# ospi_v142.net
KiCad netlist of a schematic drawn in EAGLE
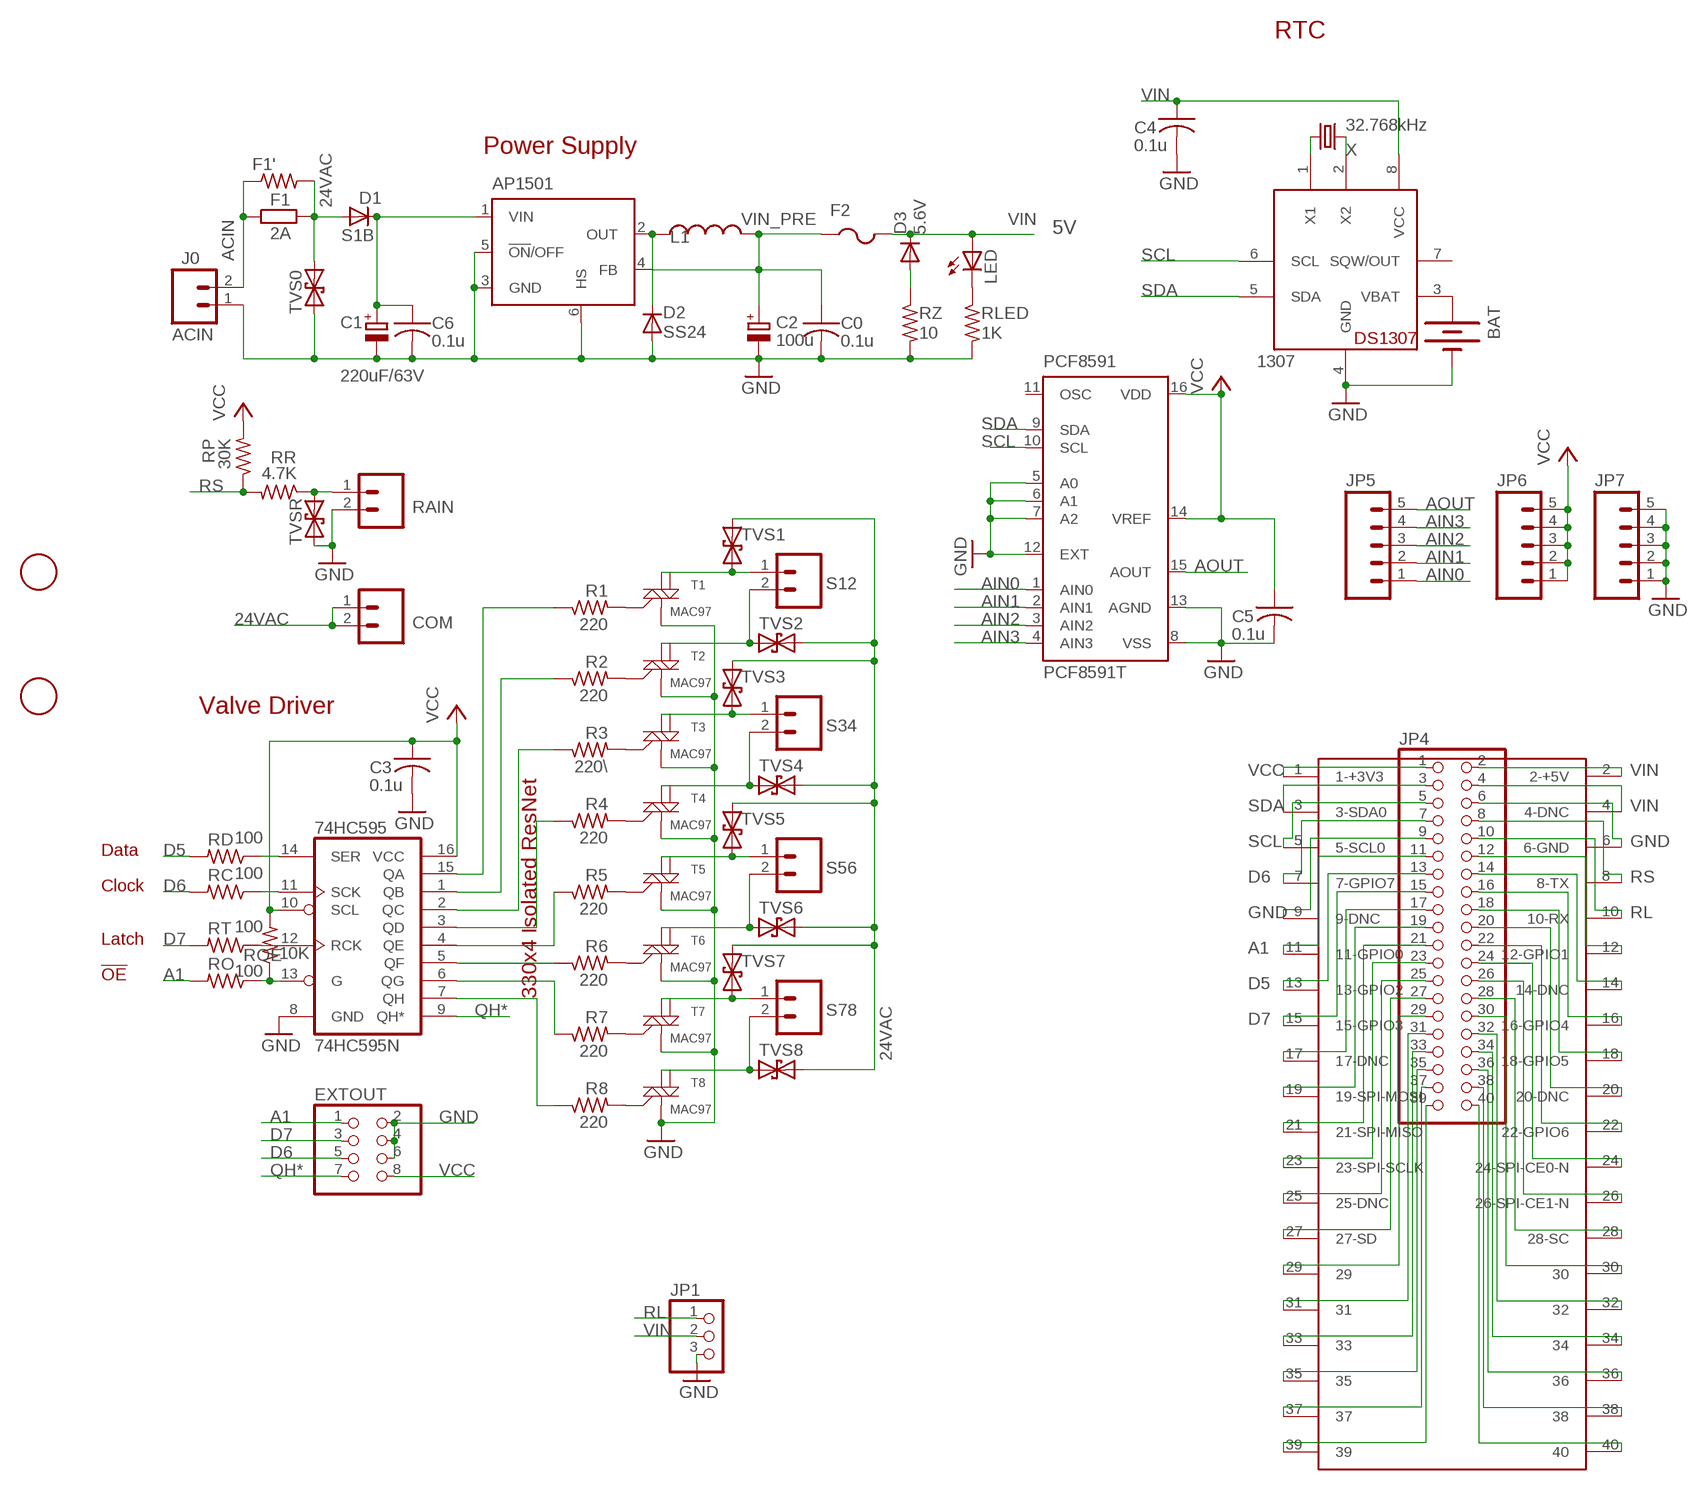
[diagram p0: schematic, sheet 1]

(export (version "E")
  (design (tool "Eeschema 10.0.6"))
  (components
    (comp (ref "74HC595")
      (value "74HC595N")
      (footprint "eagle-import:SO16")
      (libsource (lib "eagle-import") (part "74595DLS"))
    )
    (comp (ref "1307")
      (value "DS1307")
      (footprint "eagle-import:SO08")
      (libsource (lib "eagle-import") (part "DS1307SOIC"))
    )
    (comp (ref "AP1501")
      (value "LM2596S")
      (footprint "eagle-import:TO263-5")
      (fields (field (name "MF") "NATIONAL SEMICONDUCTOR") (field (name "MPN") "LM2596S-ADJ/NOPB"))
      (libsource (lib "eagle-import") (part "LM2596S"))
    )
    (comp (ref "BAT")
      (value "BATTERYBATTERY_12MM_SMT")
      (footprint "eagle-import:BATTCON_12MM_SMT")
      (libsource (lib "eagle-import") (part "BATTERYBATTERY_12MM_SMT"))
    )
    (comp (ref "C0")
      (value "0.1u")
      (footprint "eagle-import:C0603K")
      (libsource (lib "eagle-import") (part "C-USC0603K"))
    )
    (comp (ref "C1")
      (value "220uF/63V")
      (footprint "eagle-import:PANASONIC_E")
      (libsource (lib "eagle-import") (part "CPOL-EUE"))
    )
    (comp (ref "C2")
      (value "100u")
      (footprint "eagle-import:PANASONIC_E")
      (libsource (lib "eagle-import") (part "CPOL-EUE"))
    )
    (comp (ref "C3")
      (value "0.1u")
      (footprint "eagle-import:C0603K")
      (libsource (lib "eagle-import") (part "C-USC0603K"))
    )
    (comp (ref "C4")
      (value "0.1u")
      (footprint "eagle-import:C0603K")
      (libsource (lib "eagle-import") (part "C-USC0603K"))
    )
    (comp (ref "C5")
      (value "0.1u")
      (footprint "eagle-import:C0603K")
      (libsource (lib "eagle-import") (part "C-USC0603K"))
    )
    (comp (ref "C6")
      (value "0.1u")
      (footprint "eagle-import:C0603K")
      (libsource (lib "eagle-import") (part "C-USC0603K"))
    )
    (comp (ref "COM")
      (value "M025MM-X")
      (footprint "eagle-import:SCREWTERMINAL-5MM-2-X")
      (libsource (lib "eagle-import") (part "M025MM-X"))
    )
    (comp (ref "D1")
      (value "S1B")
      (footprint "eagle-import:DO-214AC")
      (libsource (lib "eagle-import") (part "DIODE-DO-214AC"))
    )
    (comp (ref "D2")
      (value "SS24")
      (footprint "eagle-import:SMB")
      (libsource (lib "eagle-import") (part "DIODE-SMB"))
    )
    (comp (ref "D3")
      (value "5.6V")
      (footprint "eagle-import:MINIMELF")
      (libsource (lib "eagle-import") (part "DIODE-MINIMELF"))
    )
    (comp (ref "EXTOUT")
      (value "PINHD-2X4/90")
      (footprint "eagle-import:2X04_90")
      (libsource (lib "eagle-import") (part "PINHD-2X4/90"))
    )
    (comp (ref "F1")
      (value "2A")
      (footprint "eagle-import:0414V")
      (libsource (lib "eagle-import") (part "R-EU_0414/5V"))
    )
    (comp (ref "F1'")
      (value "R-US_R1206")
      (footprint "eagle-import:R1206")
      (libsource (lib "eagle-import") (part "adafruitGood_R-US_R1206"))
    )
    (comp (ref "F2")
      (value "PTCFUSE-1812")
      (footprint "eagle-import:1812")
      (libsource (lib "eagle-import") (part "PTCFUSE-1812"))
    )
    (comp (ref "J0")
      (value "ACIN")
      (footprint "eagle-import:SCREWTERMINAL-4MM-2-X")
      (libsource (lib "eagle-import") (part "M024MM-X"))
    )
    (comp (ref "JP1")
      (value "PINHD-1X3")
      (footprint "eagle-import:1X03")
      (libsource (lib "eagle-import") (part "PINHD-1X3"))
    )
    (comp (ref "JP4")
      (value "PINHD-2X20")
      (footprint "eagle-import:2X20")
      (libsource (lib "eagle-import") (part "PINHD-2X20"))
    )
    (comp (ref "JP5")
      (value "M05PTH")
      (footprint "eagle-import:1X05")
      (libsource (lib "eagle-import") (part "M05PTH"))
    )
    (comp (ref "JP6")
      (value "M05PTH")
      (footprint "eagle-import:1X05")
      (libsource (lib "eagle-import") (part "M05PTH"))
    )
    (comp (ref "JP7")
      (value "M05PTH")
      (footprint "eagle-import:1X05")
      (libsource (lib "eagle-import") (part "M05PTH"))
    )
    (comp (ref "L1")
      (value "150uH")
      (footprint "eagle-import:CDRH125")
      (libsource (lib "eagle-import") (part "INDUCTORPWR"))
    )
    (comp (ref "LED")
      (value "LEDCHIPLED_0805")
      (footprint "eagle-import:CHIPLED_0805")
      (libsource (lib "eagle-import") (part "LEDCHIPLED_0805"))
    )
    (comp (ref "PCF8591")
      (value "PCF8591T")
      (footprint "eagle-import:SO16W")
      (fields (field (name "MPN") "PCF8591T/2,512"))
      (libsource (lib "eagle-import") (part "PCF8591T"))
    )
    (comp (ref "R1")
      (value "220")
      (footprint "eagle-import:R0603")
      (libsource (lib "eagle-import") (part "R-US_R0603"))
    )
    (comp (ref "R2")
      (value "220")
      (footprint "eagle-import:R0603")
      (libsource (lib "eagle-import") (part "R-US_R0603"))
    )
    (comp (ref "R3")
      (value "220\\")
      (footprint "eagle-import:R0603")
      (libsource (lib "eagle-import") (part "R-US_R0603"))
    )
    (comp (ref "R4")
      (value "220")
      (footprint "eagle-import:R0603")
      (libsource (lib "eagle-import") (part "R-US_R0603"))
    )
    (comp (ref "R5")
      (value "220")
      (footprint "eagle-import:R0603")
      (libsource (lib "eagle-import") (part "R-US_R0603"))
    )
    (comp (ref "R6")
      (value "220")
      (footprint "eagle-import:R0603")
      (libsource (lib "eagle-import") (part "R-US_R0603"))
    )
    (comp (ref "R7")
      (value "220")
      (footprint "eagle-import:R0603")
      (libsource (lib "eagle-import") (part "R-US_R0603"))
    )
    (comp (ref "R8")
      (value "220")
      (footprint "eagle-import:R0603")
      (libsource (lib "eagle-import") (part "R-US_R0603"))
    )
    (comp (ref "RAIN")
      (value "M025MM-X")
      (footprint "eagle-import:SCREWTERMINAL-5MM-2-X")
      (libsource (lib "eagle-import") (part "M025MM-X"))
    )
    (comp (ref "RC")
      (value "100")
      (footprint "eagle-import:R0603")
      (libsource (lib "eagle-import") (part "R-US_R0603"))
    )
    (comp (ref "RD")
      (value "100")
      (footprint "eagle-import:R0603")
      (libsource (lib "eagle-import") (part "R-US_R0603"))
    )
    (comp (ref "RLED")
      (value "1K")
      (footprint "eagle-import:R0805")
      (libsource (lib "eagle-import") (part "R-US_R0805"))
    )
    (comp (ref "RO")
      (value "100")
      (footprint "eagle-import:R0603")
      (libsource (lib "eagle-import") (part "R-US_R0603"))
    )
    (comp (ref "ROE")
      (value "10K")
      (footprint "eagle-import:R0603")
      (libsource (lib "eagle-import") (part "R-US_R0603"))
    )
    (comp (ref "RP")
      (value "30K")
      (footprint "eagle-import:R0805")
      (libsource (lib "eagle-import") (part "R-US_R0805"))
    )
    (comp (ref "RR")
      (value "4.7K")
      (footprint "eagle-import:R0805")
      (libsource (lib "eagle-import") (part "R-US_R0805"))
    )
    (comp (ref "RT")
      (value "100")
      (footprint "eagle-import:R0603")
      (libsource (lib "eagle-import") (part "R-US_R0603"))
    )
    (comp (ref "RZ")
      (value "10")
      (footprint "eagle-import:R0805")
      (libsource (lib "eagle-import") (part "R-US_R0805"))
    )
    (comp (ref "S12")
      (value "M025MM-X")
      (footprint "eagle-import:SCREWTERMINAL-5MM-2-X")
      (libsource (lib "eagle-import") (part "M025MM-X"))
    )
    (comp (ref "S34")
      (value "M025MM-X")
      (footprint "eagle-import:SCREWTERMINAL-5MM-2-X")
      (libsource (lib "eagle-import") (part "M025MM-X"))
    )
    (comp (ref "S56")
      (value "M025MM-X")
      (footprint "eagle-import:SCREWTERMINAL-5MM-2-X")
      (libsource (lib "eagle-import") (part "M025MM-X"))
    )
    (comp (ref "S78")
      (value "M025MM-X")
      (footprint "eagle-import:SCREWTERMINAL-5MM-2-X")
      (libsource (lib "eagle-import") (part "M025MM-X"))
    )
    (comp (ref "T1")
      (value "MAC97")
      (footprint "eagle-import:SOT223")
      (libsource (lib "eagle-import") (part "MAC97SOT223"))
    )
    (comp (ref "T2")
      (value "MAC97")
      (footprint "eagle-import:SOT223")
      (libsource (lib "eagle-import") (part "MAC97SOT223"))
    )
    (comp (ref "T3")
      (value "MAC97")
      (footprint "eagle-import:SOT223")
      (libsource (lib "eagle-import") (part "MAC97SOT223"))
    )
    (comp (ref "T4")
      (value "MAC97")
      (footprint "eagle-import:SOT223")
      (libsource (lib "eagle-import") (part "MAC97SOT223"))
    )
    (comp (ref "T5")
      (value "MAC97")
      (footprint "eagle-import:SOT223")
      (libsource (lib "eagle-import") (part "MAC97SOT223"))
    )
    (comp (ref "T6")
      (value "MAC97")
      (footprint "eagle-import:SOT223")
      (libsource (lib "eagle-import") (part "MAC97SOT223"))
    )
    (comp (ref "T7")
      (value "MAC97")
      (footprint "eagle-import:SOT223")
      (libsource (lib "eagle-import") (part "MAC97SOT223"))
    )
    (comp (ref "T8")
      (value "MAC97")
      (footprint "eagle-import:SOT223")
      (libsource (lib "eagle-import") (part "MAC97SOT223"))
    )
    (comp (ref "TVS0")
      (value "TVSSMB")
      (footprint "eagle-import:SMB")
      (libsource (lib "eagle-import") (part "TVSSMB"))
    )
    (comp (ref "TVS1")
      (value "TVSSMB")
      (footprint "eagle-import:SMB")
      (libsource (lib "eagle-import") (part "TVSSMB"))
    )
    (comp (ref "TVS2")
      (value "TVSSMB")
      (footprint "eagle-import:SMB")
      (libsource (lib "eagle-import") (part "TVSSMB"))
    )
    (comp (ref "TVS3")
      (value "TVSSMB")
      (footprint "eagle-import:SMB")
      (libsource (lib "eagle-import") (part "TVSSMB"))
    )
    (comp (ref "TVS4")
      (value "TVSSMB")
      (footprint "eagle-import:SMB")
      (libsource (lib "eagle-import") (part "TVSSMB"))
    )
    (comp (ref "TVS5")
      (value "TVSSMB")
      (footprint "eagle-import:SMB")
      (libsource (lib "eagle-import") (part "TVSSMB"))
    )
    (comp (ref "TVS6")
      (value "TVSSMB")
      (footprint "eagle-import:SMB")
      (libsource (lib "eagle-import") (part "TVSSMB"))
    )
    (comp (ref "TVS7")
      (value "TVSSMB")
      (footprint "eagle-import:SMB")
      (libsource (lib "eagle-import") (part "TVSSMB"))
    )
    (comp (ref "TVS8")
      (value "TVSSMB")
      (footprint "eagle-import:SMB")
      (libsource (lib "eagle-import") (part "TVSSMB"))
    )
    (comp (ref "TVSR")
      (value "TVSSMB")
      (footprint "eagle-import:SMB")
      (libsource (lib "eagle-import") (part "TVSSMB"))
    )
    (comp (ref "U$1")
      (value "FIDUCIAL")
      (footprint "eagle-import:FIDUCIAL_1MM")
      (libsource (lib "eagle-import") (part "FIDUCIAL"))
    )
    (comp (ref "U$2")
      (value "RPIB+")
      (footprint "eagle-import:RPIB+")
      (libsource (lib "eagle-import") (part "RPIB+"))
    )
    (comp (ref "U$3")
      (value "FIDUCIAL")
      (footprint "eagle-import:FIDUCIAL_1MM")
      (libsource (lib "eagle-import") (part "FIDUCIAL"))
    )
    (comp (ref "X")
      (value "32.768kHz")
      (footprint "eagle-import:MM20SS")
      (libsource (lib "eagle-import") (part "CRYSTALMM20SS"))
    )
  )
  (nets
    (net (code "1") (name "/24VAC") (class "Default")
      (node (ref "COM") (pin "1") (pinfunction "1_1") (pintype "passive"))
      (node (ref "COM") (pin "2") (pinfunction "2_2") (pintype "passive"))
      (node (ref "D1") (pin "A") (pinfunction "A_A") (pintype "passive"))
      (node (ref "F1") (pin "2") (pinfunction "2_2") (pintype "passive"))
      (node (ref "F1'") (pin "2") (pinfunction "2_2") (pintype "passive"))
      (node (ref "TVS0") (pin "C") (pinfunction "C_C") (pintype "passive"))
      (node (ref "TVS1") (pin "C") (pinfunction "C_C") (pintype "passive"))
      (node (ref "TVS2") (pin "C") (pinfunction "C_C") (pintype "passive"))
      (node (ref "TVS3") (pin "C") (pinfunction "C_C") (pintype "passive"))
      (node (ref "TVS4") (pin "C") (pinfunction "C_C") (pintype "passive"))
      (node (ref "TVS5") (pin "C") (pinfunction "C_C") (pintype "passive"))
      (node (ref "TVS6") (pin "C") (pinfunction "C_C") (pintype "passive"))
      (node (ref "TVS7") (pin "C") (pinfunction "C_C") (pintype "passive"))
      (node (ref "TVS8") (pin "C") (pinfunction "C_C") (pintype "passive"))
    )
    (net (code "2") (name "/A1") (class "Default")
      (node (ref "EXTOUT") (pin "1") (pinfunction "1_1") (pintype "passive"))
      (node (ref "JP4") (pin "11") (pinfunction "11_11") (pintype "passive"))
      (node (ref "RO") (pin "2") (pinfunction "2_2") (pintype "passive"))
      (node (ref "U$2") (pin "11") (pinfunction "11-GPIO0_11") (pintype "bidirectional"))
    )
    (net (code "3") (name "/ACIN") (class "Default")
      (node (ref "F1") (pin "1") (pinfunction "1_1") (pintype "passive"))
      (node (ref "F1'") (pin "1") (pinfunction "1_1") (pintype "passive"))
      (node (ref "J0") (pin "2") (pinfunction "2_2") (pintype "passive"))
    )
    (net (code "4") (name "/AIN0") (class "Default")
      (node (ref "JP5") (pin "1") (pinfunction "1_1") (pintype "passive"))
      (node (ref "PCF8591") (pin "1") (pinfunction "AIN0_1") (pintype "input"))
    )
    (net (code "5") (name "/AIN1") (class "Default")
      (node (ref "JP5") (pin "2") (pinfunction "2_2") (pintype "passive"))
      (node (ref "PCF8591") (pin "2") (pinfunction "AIN1_2") (pintype "input"))
    )
    (net (code "6") (name "/AIN2") (class "Default")
      (node (ref "JP5") (pin "3") (pinfunction "3_3") (pintype "passive"))
      (node (ref "PCF8591") (pin "3") (pinfunction "AIN2_3") (pintype "input"))
    )
    (net (code "7") (name "/AIN3") (class "Default")
      (node (ref "JP5") (pin "4") (pinfunction "4_4") (pintype "passive"))
      (node (ref "PCF8591") (pin "4") (pinfunction "AIN3_4") (pintype "input"))
    )
    (net (code "8") (name "/AOUT") (class "Default")
      (node (ref "JP5") (pin "5") (pinfunction "5_5") (pintype "passive"))
      (node (ref "PCF8591") (pin "15") (pinfunction "AOUT_15") (pintype "output"))
    )
    (net (code "9") (name "/D5") (class "Default")
      (node (ref "JP4") (pin "13") (pinfunction "13_13") (pintype "passive"))
      (node (ref "RD") (pin "2") (pinfunction "2_2") (pintype "passive"))
      (node (ref "U$2") (pin "13") (pinfunction "13-GPIO2_13") (pintype "bidirectional"))
    )
    (net (code "10") (name "/D6") (class "Default")
      (node (ref "EXTOUT") (pin "5") (pinfunction "5_5") (pintype "passive"))
      (node (ref "JP4") (pin "7") (pinfunction "7_7") (pintype "passive"))
      (node (ref "RC") (pin "2") (pinfunction "2_2") (pintype "passive"))
      (node (ref "U$2") (pin "7") (pinfunction "7-GPIO7_7") (pintype "bidirectional"))
    )
    (net (code "11") (name "/D7") (class "Default")
      (node (ref "EXTOUT") (pin "3") (pinfunction "3_3") (pintype "passive"))
      (node (ref "JP4") (pin "15") (pinfunction "15_15") (pintype "passive"))
      (node (ref "RT") (pin "2") (pinfunction "2_2") (pintype "passive"))
      (node (ref "U$2") (pin "15") (pinfunction "15-GPIO3_15") (pintype "bidirectional"))
    )
    (net (code "12") (name "/QH*") (class "Default")
      (node (ref "74HC595") (pin "9") (pinfunction "QH*_9") (pintype "tri_state"))
      (node (ref "EXTOUT") (pin "7") (pinfunction "7_7") (pintype "passive"))
    )
    (net (code "13") (name "/RL") (class "Default")
      (node (ref "JP1") (pin "1") (pinfunction "1_1") (pintype "passive"))
      (node (ref "JP4") (pin "10") (pinfunction "10_10") (pintype "passive"))
      (node (ref "U$2") (pin "10") (pinfunction "10-RX_10") (pintype "bidirectional"))
    )
    (net (code "14") (name "/RS") (class "Default")
      (node (ref "JP4") (pin "8") (pinfunction "8_8") (pintype "passive"))
      (node (ref "RP") (pin "1") (pinfunction "1_1") (pintype "passive"))
      (node (ref "RR") (pin "2") (pinfunction "2_2") (pintype "passive"))
      (node (ref "U$2") (pin "8") (pinfunction "8-TX_8") (pintype "bidirectional"))
    )
    (net (code "15") (name "/SCL") (class "Default")
      (node (ref "1307") (pin "6") (pinfunction "SCL_6") (pintype "bidirectional"))
      (node (ref "JP4") (pin "5") (pinfunction "5_5") (pintype "passive"))
      (node (ref "PCF8591") (pin "10") (pinfunction "SCL_10") (pintype "input"))
      (node (ref "U$2") (pin "5") (pinfunction "5-SCL0_5") (pintype "bidirectional"))
    )
    (net (code "16") (name "/SDA") (class "Default")
      (node (ref "1307") (pin "5") (pinfunction "SDA_5") (pintype "bidirectional"))
      (node (ref "JP4") (pin "3") (pinfunction "3_3") (pintype "passive"))
      (node (ref "PCF8591") (pin "9") (pinfunction "SDA_9") (pintype "bidirectional"))
      (node (ref "U$2") (pin "3") (pinfunction "3-SDA0_3") (pintype "bidirectional"))
    )
    (net (code "17") (name "/VIN") (class "Default")
      (node (ref "1307") (pin "8") (pinfunction "VCC_8") (pintype "power_in"))
      (node (ref "C4") (pin "1") (pinfunction "1_1") (pintype "passive"))
      (node (ref "D3") (pin "C") (pinfunction "C_C") (pintype "passive"))
      (node (ref "F2") (pin "2") (pinfunction "2_2") (pintype "passive"))
      (node (ref "JP1") (pin "2") (pinfunction "2_2") (pintype "passive"))
      (node (ref "JP4") (pin "2") (pinfunction "2_2") (pintype "passive"))
      (node (ref "JP4") (pin "4") (pinfunction "4_4") (pintype "passive"))
      (node (ref "LED") (pin "A") (pinfunction "A_A") (pintype "passive"))
      (node (ref "U$2") (pin "2") (pinfunction "2-+5V_2") (pintype "bidirectional"))
      (node (ref "U$2") (pin "4") (pinfunction "4-DNC_4") (pintype "bidirectional"))
    )
    (net (code "18") (name "/VIN_PRE") (class "Default")
      (node (ref "AP1501") (pin "4") (pinfunction "FB_4") (pintype "input"))
      (node (ref "C0") (pin "1") (pinfunction "1_1") (pintype "passive"))
      (node (ref "C2") (pin "+") (pinfunction "+_+") (pintype "passive"))
      (node (ref "F2") (pin "1") (pinfunction "1_1") (pintype "passive"))
      (node (ref "L1") (pin "2") (pinfunction "2_2") (pintype "passive"))
    )
    (net (code "19") (name "GND") (class "Default")
      (node (ref "1307") (pin "4") (pinfunction "GND_4") (pintype "power_in"))
      (node (ref "74HC595") (pin "8") (pinfunction "GND_8") (pintype "power_in"))
      (node (ref "AP1501") (pin "3") (pinfunction "GND_3") (pintype "power_in"))
      (node (ref "AP1501") (pin "5") (pinfunction "~{ON}/OFF_5") (pintype "input"))
      (node (ref "AP1501") (pin "6") (pinfunction "HS_6") (pintype "power_in"))
      (node (ref "BAT") (pin "P$1") (pinfunction "-_P$1") (pintype "power_in"))
      (node (ref "C0") (pin "2") (pinfunction "2_2") (pintype "passive"))
      (node (ref "C1") (pin "-") (pinfunction "-_-") (pintype "passive"))
      (node (ref "C2") (pin "-") (pinfunction "-_-") (pintype "passive"))
      (node (ref "C3") (pin "2") (pinfunction "2_2") (pintype "passive"))
      (node (ref "C4") (pin "2") (pinfunction "2_2") (pintype "passive"))
      (node (ref "C5") (pin "2") (pinfunction "2_2") (pintype "passive"))
      (node (ref "C6") (pin "2") (pinfunction "2_2") (pintype "passive"))
      (node (ref "D2") (pin "A") (pinfunction "A_A") (pintype "passive"))
      (node (ref "EXTOUT") (pin "2") (pinfunction "2_2") (pintype "passive"))
      (node (ref "EXTOUT") (pin "4") (pinfunction "4_4") (pintype "passive"))
      (node (ref "EXTOUT") (pin "6") (pinfunction "6_6") (pintype "passive"))
      (node (ref "J0") (pin "1") (pinfunction "1_1") (pintype "passive"))
      (node (ref "JP1") (pin "3") (pinfunction "3_3") (pintype "passive"))
      (node (ref "JP4") (pin "6") (pinfunction "6_6") (pintype "passive"))
      (node (ref "JP4") (pin "9") (pinfunction "9_9") (pintype "passive"))
      (node (ref "JP7") (pin "1") (pinfunction "1_1") (pintype "passive"))
      (node (ref "JP7") (pin "2") (pinfunction "2_2") (pintype "passive"))
      (node (ref "JP7") (pin "3") (pinfunction "3_3") (pintype "passive"))
      (node (ref "JP7") (pin "4") (pinfunction "4_4") (pintype "passive"))
      (node (ref "JP7") (pin "5") (pinfunction "5_5") (pintype "passive"))
      (node (ref "PCF8591") (pin "12") (pinfunction "EXT_12") (pintype "input"))
      (node (ref "PCF8591") (pin "13") (pinfunction "AGND_13") (pintype "power_in"))
      (node (ref "PCF8591") (pin "5") (pinfunction "A0_5") (pintype "input"))
      (node (ref "PCF8591") (pin "6") (pinfunction "A1_6") (pintype "input"))
      (node (ref "PCF8591") (pin "7") (pinfunction "A2_7") (pintype "input"))
      (node (ref "PCF8591") (pin "8") (pinfunction "VSS_8") (pintype "power_in"))
      (node (ref "RAIN") (pin "2") (pinfunction "2_2") (pintype "passive"))
      (node (ref "RLED") (pin "2") (pinfunction "2_2") (pintype "passive"))
      (node (ref "RZ") (pin "2") (pinfunction "2_2") (pintype "passive"))
      (node (ref "T1") (pin "1") (pinfunction "M1_1") (pintype "bidirectional"))
      (node (ref "T2") (pin "1") (pinfunction "M1_1") (pintype "bidirectional"))
      (node (ref "T3") (pin "1") (pinfunction "M1_1") (pintype "bidirectional"))
      (node (ref "T4") (pin "1") (pinfunction "M1_1") (pintype "bidirectional"))
      (node (ref "T5") (pin "1") (pinfunction "M1_1") (pintype "bidirectional"))
      (node (ref "T6") (pin "1") (pinfunction "M1_1") (pintype "bidirectional"))
      (node (ref "T7") (pin "1") (pinfunction "M1_1") (pintype "bidirectional"))
      (node (ref "T8") (pin "1") (pinfunction "M1_1") (pintype "bidirectional"))
      (node (ref "TVS0") (pin "A") (pinfunction "A_A") (pintype "passive"))
      (node (ref "TVSR") (pin "A") (pinfunction "A_A") (pintype "passive"))
      (node (ref "U$2") (pin "6") (pinfunction "6-GND_6") (pintype "bidirectional"))
      (node (ref "U$2") (pin "9") (pinfunction "9-DNC_9") (pintype "bidirectional"))
    )
    (net (code "20") (name "Net-(74HC595-G)") (class "Default")
      (node (ref "74HC595") (pin "13") (pinfunction "G_13") (pintype "input"))
      (node (ref "RO") (pin "1") (pinfunction "1_1") (pintype "passive"))
      (node (ref "ROE") (pin "1") (pinfunction "1_1") (pintype "passive"))
    )
    (net (code "21") (name "Net-(74HC595-QA)") (class "Default")
      (node (ref "74HC595") (pin "15") (pinfunction "QA_15") (pintype "tri_state"))
      (node (ref "R1") (pin "1") (pinfunction "1_1") (pintype "passive"))
    )
    (net (code "22") (name "Net-(74HC595-QB)") (class "Default")
      (node (ref "74HC595") (pin "1") (pinfunction "QB_1") (pintype "tri_state"))
      (node (ref "R2") (pin "1") (pinfunction "1_1") (pintype "passive"))
    )
    (net (code "23") (name "Net-(74HC595-QC)") (class "Default")
      (node (ref "74HC595") (pin "2") (pinfunction "QC_2") (pintype "tri_state"))
      (node (ref "R3") (pin "1") (pinfunction "1_1") (pintype "passive"))
    )
    (net (code "24") (name "Net-(74HC595-QD)") (class "Default")
      (node (ref "74HC595") (pin "3") (pinfunction "QD_3") (pintype "tri_state"))
      (node (ref "R4") (pin "1") (pinfunction "1_1") (pintype "passive"))
    )
    (net (code "25") (name "Net-(74HC595-QE)") (class "Default")
      (node (ref "74HC595") (pin "4") (pinfunction "QE_4") (pintype "tri_state"))
      (node (ref "R5") (pin "1") (pinfunction "1_1") (pintype "passive"))
    )
    (net (code "26") (name "Net-(74HC595-QF)") (class "Default")
      (node (ref "74HC595") (pin "5") (pinfunction "QF_5") (pintype "tri_state"))
      (node (ref "R6") (pin "1") (pinfunction "1_1") (pintype "passive"))
    )
    (net (code "27") (name "Net-(74HC595-QG)") (class "Default")
      (node (ref "74HC595") (pin "6") (pinfunction "QG_6") (pintype "tri_state"))
      (node (ref "R7") (pin "1") (pinfunction "1_1") (pintype "passive"))
    )
    (net (code "28") (name "Net-(74HC595-QH)") (class "Default")
      (node (ref "74HC595") (pin "7") (pinfunction "QH_7") (pintype "tri_state"))
      (node (ref "R8") (pin "1") (pinfunction "1_1") (pintype "passive"))
    )
    (net (code "29") (name "Net-(74HC595-RCK)") (class "Default")
      (node (ref "74HC595") (pin "12") (pinfunction "RCK_12") (pintype "input"))
      (node (ref "RT") (pin "1") (pinfunction "1_1") (pintype "passive"))
    )
    (net (code "30") (name "Net-(74HC595-SCK)") (class "Default")
      (node (ref "74HC595") (pin "11") (pinfunction "SCK_11") (pintype "input"))
      (node (ref "RC") (pin "1") (pinfunction "1_1") (pintype "passive"))
    )
    (net (code "31") (name "Net-(74HC595-SER)") (class "Default")
      (node (ref "74HC595") (pin "14") (pinfunction "SER_14") (pintype "input"))
      (node (ref "RD") (pin "1") (pinfunction "1_1") (pintype "passive"))
    )
    (net (code "32") (name "Net-(1307-VBAT)") (class "Default")
      (node (ref "1307") (pin "3") (pinfunction "VBAT_3") (pintype "power_in"))
      (node (ref "BAT") (pin "P$2") (pinfunction "+_P$2") (pintype "power_in"))
    )
    (net (code "33") (name "Net-(1307-X1)") (class "Default")
      (node (ref "1307") (pin "1") (pinfunction "X1_1") (pintype "passive"))
      (node (ref "X") (pin "1") (pinfunction "1_1") (pintype "passive"))
    )
    (net (code "34") (name "Net-(1307-X2)") (class "Default")
      (node (ref "1307") (pin "2") (pinfunction "X2_2") (pintype "passive"))
      (node (ref "X") (pin "4") (pinfunction "2_4") (pintype "passive"))
    )
    (net (code "35") (name "Net-(AP1501-OUT)") (class "Default")
      (node (ref "AP1501") (pin "2") (pinfunction "OUT_2") (pintype "output"))
      (node (ref "D2") (pin "C") (pinfunction "C_C") (pintype "passive"))
      (node (ref "L1") (pin "1") (pinfunction "1_1") (pintype "passive"))
    )
    (net (code "36") (name "Net-(AP1501-VIN)") (class "Default")
      (node (ref "AP1501") (pin "1") (pinfunction "VIN_1") (pintype "input"))
      (node (ref "C1") (pin "+") (pinfunction "+_+") (pintype "passive"))
      (node (ref "C6") (pin "1") (pinfunction "1_1") (pintype "passive"))
      (node (ref "D1") (pin "C") (pinfunction "C_C") (pintype "passive"))
    )
    (net (code "37") (name "Net-(D3-PadA)") (class "Default")
      (node (ref "D3") (pin "A") (pinfunction "A_A") (pintype "passive"))
      (node (ref "RZ") (pin "1") (pinfunction "1_1") (pintype "passive"))
    )
    (net (code "38") (name "Net-(JP4-Pad29)") (class "Default")
      (node (ref "JP4") (pin "29") (pinfunction "29_29") (pintype "passive"))
      (node (ref "U$2") (pin "29") (pinfunction "29_29") (pintype "bidirectional"))
    )
    (net (code "39") (name "Net-(JP4-Pad30)") (class "Default")
      (node (ref "JP4") (pin "30") (pinfunction "30_30") (pintype "passive"))
      (node (ref "U$2") (pin "30") (pinfunction "30_30") (pintype "bidirectional"))
    )
    (net (code "40") (name "Net-(JP4-Pad31)") (class "Default")
      (node (ref "JP4") (pin "31") (pinfunction "31_31") (pintype "passive"))
      (node (ref "U$2") (pin "31") (pinfunction "31_31") (pintype "bidirectional"))
    )
    (net (code "41") (name "Net-(JP4-Pad32)") (class "Default")
      (node (ref "JP4") (pin "32") (pinfunction "32_32") (pintype "passive"))
      (node (ref "U$2") (pin "32") (pinfunction "32_32") (pintype "bidirectional"))
    )
    (net (code "42") (name "Net-(JP4-Pad33)") (class "Default")
      (node (ref "JP4") (pin "33") (pinfunction "33_33") (pintype "passive"))
      (node (ref "U$2") (pin "33") (pinfunction "33_33") (pintype "bidirectional"))
    )
    (net (code "43") (name "Net-(JP4-Pad34)") (class "Default")
      (node (ref "JP4") (pin "34") (pinfunction "34_34") (pintype "passive"))
      (node (ref "U$2") (pin "34") (pinfunction "34_34") (pintype "bidirectional"))
    )
    (net (code "44") (name "Net-(JP4-Pad35)") (class "Default")
      (node (ref "JP4") (pin "35") (pinfunction "35_35") (pintype "passive"))
      (node (ref "U$2") (pin "35") (pinfunction "35_35") (pintype "bidirectional"))
    )
    (net (code "45") (name "Net-(JP4-Pad36)") (class "Default")
      (node (ref "JP4") (pin "36") (pinfunction "36_36") (pintype "passive"))
      (node (ref "U$2") (pin "36") (pinfunction "36_36") (pintype "bidirectional"))
    )
    (net (code "46") (name "Net-(JP4-Pad37)") (class "Default")
      (node (ref "JP4") (pin "37") (pinfunction "37_37") (pintype "passive"))
      (node (ref "U$2") (pin "37") (pinfunction "37_37") (pintype "bidirectional"))
    )
    (net (code "47") (name "Net-(JP4-Pad38)") (class "Default")
      (node (ref "JP4") (pin "38") (pinfunction "38_38") (pintype "passive"))
      (node (ref "U$2") (pin "38") (pinfunction "38_38") (pintype "bidirectional"))
    )
    (net (code "48") (name "Net-(JP4-Pad39)") (class "Default")
      (node (ref "JP4") (pin "39") (pinfunction "39_39") (pintype "passive"))
      (node (ref "U$2") (pin "39") (pinfunction "39_39") (pintype "bidirectional"))
    )
    (net (code "49") (name "Net-(JP4-Pad40)") (class "Default")
      (node (ref "JP4") (pin "40") (pinfunction "40_40") (pintype "passive"))
      (node (ref "U$2") (pin "40") (pinfunction "40_40") (pintype "bidirectional"))
    )
    (net (code "50") (name "Net-(LED-PadC)") (class "Default")
      (node (ref "LED") (pin "C") (pinfunction "C_C") (pintype "passive"))
      (node (ref "RLED") (pin "1") (pinfunction "1_1") (pintype "passive"))
    )
    (net (code "51") (name "Net-(RAIN-Pad1)") (class "Default")
      (node (ref "RAIN") (pin "1") (pinfunction "1_1") (pintype "passive"))
      (node (ref "RR") (pin "1") (pinfunction "1_1") (pintype "passive"))
      (node (ref "TVSR") (pin "C") (pinfunction "C_C") (pintype "passive"))
    )
    (net (code "52") (name "Net-(T1-G)") (class "Default")
      (node (ref "R1") (pin "2") (pinfunction "2_2") (pintype "passive"))
      (node (ref "T1") (pin "3") (pinfunction "G_3") (pintype "bidirectional"))
    )
    (net (code "53") (name "Net-(T1-M2)") (class "Default")
      (node (ref "S12") (pin "1") (pinfunction "1_1") (pintype "passive"))
      (node (ref "T1") (pin "2") (pinfunction "M2_2") (pintype "bidirectional"))
      (node (ref "TVS1") (pin "A") (pinfunction "A_A") (pintype "passive"))
    )
    (net (code "54") (name "Net-(T2-G)") (class "Default")
      (node (ref "R2") (pin "2") (pinfunction "2_2") (pintype "passive"))
      (node (ref "T2") (pin "3") (pinfunction "G_3") (pintype "bidirectional"))
    )
    (net (code "55") (name "Net-(T2-M2)") (class "Default")
      (node (ref "S12") (pin "2") (pinfunction "2_2") (pintype "passive"))
      (node (ref "T2") (pin "2") (pinfunction "M2_2") (pintype "bidirectional"))
      (node (ref "TVS2") (pin "A") (pinfunction "A_A") (pintype "passive"))
    )
    (net (code "56") (name "Net-(T3-G)") (class "Default")
      (node (ref "R3") (pin "2") (pinfunction "2_2") (pintype "passive"))
      (node (ref "T3") (pin "3") (pinfunction "G_3") (pintype "bidirectional"))
    )
    (net (code "57") (name "Net-(T3-M2)") (class "Default")
      (node (ref "S34") (pin "1") (pinfunction "1_1") (pintype "passive"))
      (node (ref "T3") (pin "2") (pinfunction "M2_2") (pintype "bidirectional"))
      (node (ref "TVS3") (pin "A") (pinfunction "A_A") (pintype "passive"))
    )
    (net (code "58") (name "Net-(T4-G)") (class "Default")
      (node (ref "R4") (pin "2") (pinfunction "2_2") (pintype "passive"))
      (node (ref "T4") (pin "3") (pinfunction "G_3") (pintype "bidirectional"))
    )
    (net (code "59") (name "Net-(T4-M2)") (class "Default")
      (node (ref "S34") (pin "2") (pinfunction "2_2") (pintype "passive"))
      (node (ref "T4") (pin "2") (pinfunction "M2_2") (pintype "bidirectional"))
      (node (ref "TVS4") (pin "A") (pinfunction "A_A") (pintype "passive"))
    )
    (net (code "60") (name "Net-(T5-G)") (class "Default")
      (node (ref "R5") (pin "2") (pinfunction "2_2") (pintype "passive"))
      (node (ref "T5") (pin "3") (pinfunction "G_3") (pintype "bidirectional"))
    )
    (net (code "61") (name "Net-(T5-M2)") (class "Default")
      (node (ref "S56") (pin "1") (pinfunction "1_1") (pintype "passive"))
      (node (ref "T5") (pin "2") (pinfunction "M2_2") (pintype "bidirectional"))
      (node (ref "TVS5") (pin "A") (pinfunction "A_A") (pintype "passive"))
    )
    (net (code "62") (name "Net-(T6-G)") (class "Default")
      (node (ref "R6") (pin "2") (pinfunction "2_2") (pintype "passive"))
      (node (ref "T6") (pin "3") (pinfunction "G_3") (pintype "bidirectional"))
    )
    (net (code "63") (name "Net-(T6-M2)") (class "Default")
      (node (ref "S56") (pin "2") (pinfunction "2_2") (pintype "passive"))
      (node (ref "T6") (pin "2") (pinfunction "M2_2") (pintype "bidirectional"))
      (node (ref "TVS6") (pin "A") (pinfunction "A_A") (pintype "passive"))
    )
    (net (code "64") (name "Net-(T7-G)") (class "Default")
      (node (ref "R7") (pin "2") (pinfunction "2_2") (pintype "passive"))
      (node (ref "T7") (pin "3") (pinfunction "G_3") (pintype "bidirectional"))
    )
    (net (code "65") (name "Net-(T7-M2)") (class "Default")
      (node (ref "S78") (pin "1") (pinfunction "1_1") (pintype "passive"))
      (node (ref "T7") (pin "2") (pinfunction "M2_2") (pintype "bidirectional"))
      (node (ref "TVS7") (pin "A") (pinfunction "A_A") (pintype "passive"))
    )
    (net (code "66") (name "Net-(T8-G)") (class "Default")
      (node (ref "R8") (pin "2") (pinfunction "2_2") (pintype "passive"))
      (node (ref "T8") (pin "3") (pinfunction "G_3") (pintype "bidirectional"))
    )
    (net (code "67") (name "Net-(T8-M2)") (class "Default")
      (node (ref "S78") (pin "2") (pinfunction "2_2") (pintype "passive"))
      (node (ref "T8") (pin "2") (pinfunction "M2_2") (pintype "bidirectional"))
      (node (ref "TVS8") (pin "A") (pinfunction "A_A") (pintype "passive"))
    )
    (net (code "68") (name "Net-(U$2-12-GPIO1)") (class "Default")
      (node (ref "JP4") (pin "12") (pinfunction "12_12") (pintype "passive"))
      (node (ref "U$2") (pin "12") (pinfunction "12-GPIO1_12") (pintype "bidirectional"))
    )
    (net (code "69") (name "Net-(U$2-14-DNC)") (class "Default")
      (node (ref "JP4") (pin "14") (pinfunction "14_14") (pintype "passive"))
      (node (ref "U$2") (pin "14") (pinfunction "14-DNC_14") (pintype "bidirectional"))
    )
    (net (code "70") (name "Net-(U$2-16-GPIO4)") (class "Default")
      (node (ref "JP4") (pin "16") (pinfunction "16_16") (pintype "passive"))
      (node (ref "U$2") (pin "16") (pinfunction "16-GPIO4_16") (pintype "bidirectional"))
    )
    (net (code "71") (name "Net-(U$2-17-DNC)") (class "Default")
      (node (ref "JP4") (pin "17") (pinfunction "17_17") (pintype "passive"))
      (node (ref "U$2") (pin "17") (pinfunction "17-DNC_17") (pintype "bidirectional"))
    )
    (net (code "72") (name "Net-(U$2-18-GPIO5)") (class "Default")
      (node (ref "JP4") (pin "18") (pinfunction "18_18") (pintype "passive"))
      (node (ref "U$2") (pin "18") (pinfunction "18-GPIO5_18") (pintype "bidirectional"))
    )
    (net (code "73") (name "Net-(U$2-19-SPI-MOSI)") (class "Default")
      (node (ref "JP4") (pin "19") (pinfunction "19_19") (pintype "passive"))
      (node (ref "U$2") (pin "19") (pinfunction "19-SPI-MOSI_19") (pintype "bidirectional"))
    )
    (net (code "74") (name "Net-(U$2-20-DNC)") (class "Default")
      (node (ref "JP4") (pin "20") (pinfunction "20_20") (pintype "passive"))
      (node (ref "U$2") (pin "20") (pinfunction "20-DNC_20") (pintype "bidirectional"))
    )
    (net (code "75") (name "Net-(U$2-21-SPI-MISO)") (class "Default")
      (node (ref "JP4") (pin "21") (pinfunction "21_21") (pintype "passive"))
      (node (ref "U$2") (pin "21") (pinfunction "21-SPI-MISO_21") (pintype "bidirectional"))
    )
    (net (code "76") (name "Net-(U$2-22-GPIO6)") (class "Default")
      (node (ref "JP4") (pin "22") (pinfunction "22_22") (pintype "passive"))
      (node (ref "U$2") (pin "22") (pinfunction "22-GPIO6_22") (pintype "bidirectional"))
    )
    (net (code "77") (name "Net-(U$2-23-SPI-SCLK)") (class "Default")
      (node (ref "JP4") (pin "23") (pinfunction "23_23") (pintype "passive"))
      (node (ref "U$2") (pin "23") (pinfunction "23-SPI-SCLK_23") (pintype "bidirectional"))
    )
    (net (code "78") (name "Net-(U$2-24-SPI-CE0-N)") (class "Default")
      (node (ref "JP4") (pin "24") (pinfunction "24_24") (pintype "passive"))
      (node (ref "U$2") (pin "24") (pinfunction "24-SPI-CE0-N_24") (pintype "bidirectional"))
    )
    (net (code "79") (name "Net-(U$2-25-DNC)") (class "Default")
      (node (ref "JP4") (pin "25") (pinfunction "25_25") (pintype "passive"))
      (node (ref "U$2") (pin "25") (pinfunction "25-DNC_25") (pintype "bidirectional"))
    )
    (net (code "80") (name "Net-(U$2-26-SPI-CE1-N)") (class "Default")
      (node (ref "JP4") (pin "26") (pinfunction "26_26") (pintype "passive"))
      (node (ref "U$2") (pin "26") (pinfunction "26-SPI-CE1-N_26") (pintype "bidirectional"))
    )
    (net (code "81") (name "Net-(U$2-27-SD)") (class "Default")
      (node (ref "JP4") (pin "27") (pinfunction "27_27") (pintype "passive"))
      (node (ref "U$2") (pin "27") (pinfunction "27-SD_27") (pintype "bidirectional"))
    )
    (net (code "82") (name "Net-(U$2-28-SC)") (class "Default")
      (node (ref "JP4") (pin "28") (pinfunction "28_28") (pintype "passive"))
      (node (ref "U$2") (pin "28") (pinfunction "28-SC_28") (pintype "bidirectional"))
    )
    (net (code "83") (name "VCC") (class "Default")
      (node (ref "74HC595") (pin "10") (pinfunction "SCL_10") (pintype "input"))
      (node (ref "74HC595") (pin "16") (pinfunction "VCC_16") (pintype "power_in"))
      (node (ref "C3") (pin "1") (pinfunction "1_1") (pintype "passive"))
      (node (ref "C5") (pin "1") (pinfunction "1_1") (pintype "passive"))
      (node (ref "EXTOUT") (pin "8") (pinfunction "8_8") (pintype "passive"))
      (node (ref "JP4") (pin "1") (pinfunction "1_1") (pintype "passive"))
      (node (ref "JP6") (pin "1") (pinfunction "1_1") (pintype "passive"))
      (node (ref "JP6") (pin "2") (pinfunction "2_2") (pintype "passive"))
      (node (ref "JP6") (pin "3") (pinfunction "3_3") (pintype "passive"))
      (node (ref "JP6") (pin "4") (pinfunction "4_4") (pintype "passive"))
      (node (ref "JP6") (pin "5") (pinfunction "5_5") (pintype "passive"))
      (node (ref "PCF8591") (pin "14") (pinfunction "VREF_14") (pintype "input"))
      (node (ref "PCF8591") (pin "16") (pinfunction "VDD_16") (pintype "power_in"))
      (node (ref "ROE") (pin "2") (pinfunction "2_2") (pintype "passive"))
      (node (ref "RP") (pin "2") (pinfunction "2_2") (pintype "passive"))
      (node (ref "U$2") (pin "1") (pinfunction "1-+3V3_1") (pintype "bidirectional"))
    )
    (net (code "84") (name "unconnected-(1307-SQW{slash}OUT-Pad7)") (class "Default")
      (node (ref "1307") (pin "7") (pinfunction "SQW/OUT_7") (pintype "bidirectional"))
    )
    (net (code "85") (name "unconnected-(PCF8591-OSC-Pad11)") (class "Default")
      (node (ref "PCF8591") (pin "11") (pinfunction "OSC_11") (pintype "input"))
    )
    (net (code "86") (name "unconnected-(T1-M2-4-Pad4)") (class "Default")
      (node (ref "T1") (pin "4") (pinfunction "M2-4_4") (pintype "bidirectional"))
    )
    (net (code "87") (name "unconnected-(T2-M2-4-Pad4)") (class "Default")
      (node (ref "T2") (pin "4") (pinfunction "M2-4_4") (pintype "bidirectional"))
    )
    (net (code "88") (name "unconnected-(T3-M2-4-Pad4)") (class "Default")
      (node (ref "T3") (pin "4") (pinfunction "M2-4_4") (pintype "bidirectional"))
    )
    (net (code "89") (name "unconnected-(T4-M2-4-Pad4)") (class "Default")
      (node (ref "T4") (pin "4") (pinfunction "M2-4_4") (pintype "bidirectional"))
    )
    (net (code "90") (name "unconnected-(T5-M2-4-Pad4)") (class "Default")
      (node (ref "T5") (pin "4") (pinfunction "M2-4_4") (pintype "bidirectional"))
    )
    (net (code "91") (name "unconnected-(T6-M2-4-Pad4)") (class "Default")
      (node (ref "T6") (pin "4") (pinfunction "M2-4_4") (pintype "bidirectional"))
    )
    (net (code "92") (name "unconnected-(T7-M2-4-Pad4)") (class "Default")
      (node (ref "T7") (pin "4") (pinfunction "M2-4_4") (pintype "bidirectional"))
    )
    (net (code "93") (name "unconnected-(T8-M2-4-Pad4)") (class "Default")
      (node (ref "T8") (pin "4") (pinfunction "M2-4_4") (pintype "bidirectional"))
    )
  )
)
